# minsis_arduino_mcr.net
KiCad netlist of a schematic drawn in EAGLE
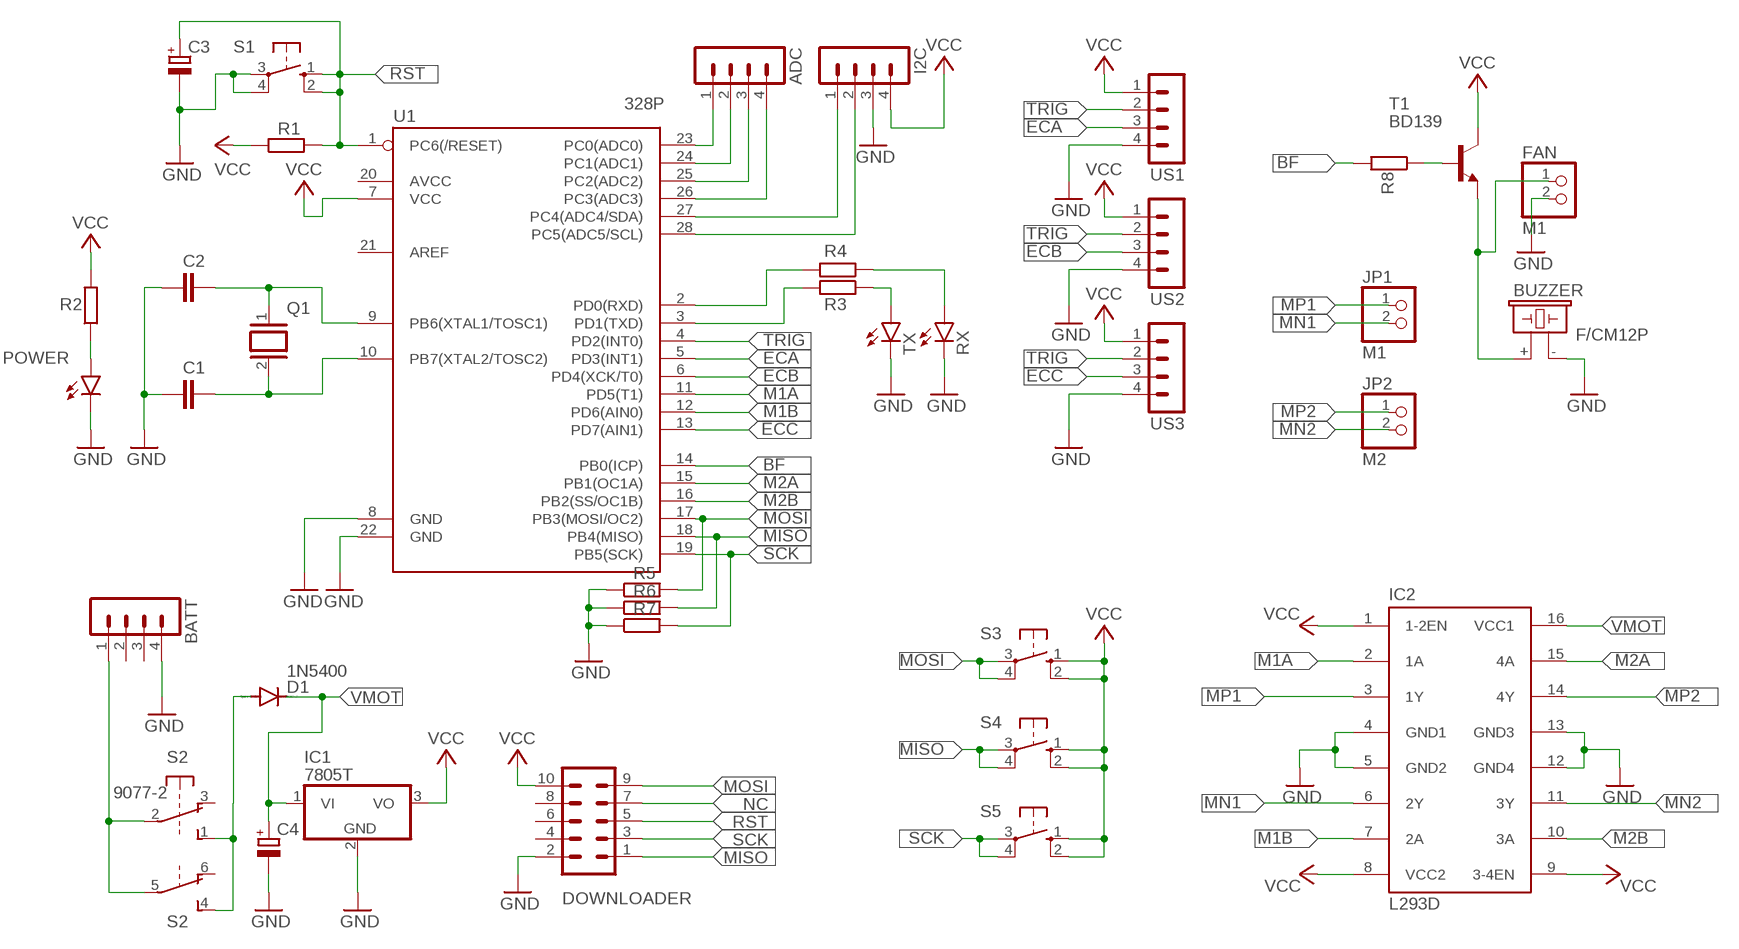
[diagram p0: schematic, sheet 1]

(export (version "E")
  (design (tool "Eeschema 10.0.6"))
  (components
    (comp (ref "ADC")
      (value "MA04-1")
      (footprint "eagle-import:MA04-1")
      (libsource (lib "eagle-import") (part "MA04-1"))
    )
    (comp (ref "BATT")
      (value "MA04-1")
      (footprint "eagle-import:MA04-1")
      (libsource (lib "eagle-import") (part "MA04-1"))
    )
    (comp (ref "BUZZER")
      (value "F/CM12P")
      (footprint "eagle-import:F_CM12P")
      (libsource (lib "eagle-import") (part "F/CM12P"))
    )
    (comp (ref "C1")
      (value "C-EU050-024X044")
      (footprint "eagle-import:C050-024X044")
      (libsource (lib "eagle-import") (part "C-EU050-024X044"))
    )
    (comp (ref "C2")
      (value "C-EU050-024X044")
      (footprint "eagle-import:C050-024X044")
      (libsource (lib "eagle-import") (part "C-EU050-024X044"))
    )
    (comp (ref "C3")
      (value "CPOL-EUE2,5-6E")
      (footprint "eagle-import:E2,5-6E")
      (libsource (lib "eagle-import") (part "CPOL-EUE2,5-6E"))
    )
    (comp (ref "C4")
      (value "CPOL-EUE3.5-8")
      (footprint "eagle-import:E3,5-8")
      (libsource (lib "eagle-import") (part "CPOL-EUE3.5-8"))
    )
    (comp (ref "D1")
      (value "1N5400")
      (footprint "eagle-import:DO201-15")
      (libsource (lib "eagle-import") (part "1N5400"))
    )
    (comp (ref "DOWNLOADER")
      (value "MA05-2")
      (footprint "eagle-import:MA05-2")
      (libsource (lib "eagle-import") (part "MA05-2"))
    )
    (comp (ref "FAN")
      (value "M1")
      (footprint "eagle-import:1X02")
      (libsource (lib "eagle-import") (part "PINHD-1X2"))
    )
    (comp (ref "I2C")
      (value "MA04-1")
      (footprint "eagle-import:MA04-1")
      (libsource (lib "eagle-import") (part "MA04-1"))
    )
    (comp (ref "IC1")
      (value "7805T")
      (footprint "eagle-import:TO220H")
      (libsource (lib "eagle-import") (part "78T05"))
    )
    (comp (ref "IC2")
      (value "L293D")
      (footprint "eagle-import:DIL16")
      (libsource (lib "eagle-import") (part "L293D"))
    )
    (comp (ref "JP1")
      (value "M1")
      (footprint "eagle-import:1X02")
      (libsource (lib "eagle-import") (part "PINHD-1X2"))
    )
    (comp (ref "JP2")
      (value "M2")
      (footprint "eagle-import:1X02")
      (libsource (lib "eagle-import") (part "PINHD-1X2"))
    )
    (comp (ref "POWER")
      (value "LED3MM")
      (footprint "eagle-import:LED3MM")
      (libsource (lib "eagle-import") (part "LED3MM"))
    )
    (comp (ref "Q1")
      (value "XTAL/S")
      (footprint "eagle-import:QS")
      (libsource (lib "eagle-import") (part "XTAL/S"))
    )
    (comp (ref "R1")
      (value "R-EU_0207/7")
      (footprint "eagle-import:0207_7")
      (libsource (lib "eagle-import") (part "R-EU_0207/7"))
    )
    (comp (ref "R2")
      (value "R-EU_0207/7")
      (footprint "eagle-import:0207_7")
      (libsource (lib "eagle-import") (part "R-EU_0207/7"))
    )
    (comp (ref "R3")
      (value "R-EU_0207/7")
      (footprint "eagle-import:0207_7")
      (libsource (lib "eagle-import") (part "R-EU_0207/7"))
    )
    (comp (ref "R4")
      (value "R-EU_0207/7")
      (footprint "eagle-import:0207_7")
      (libsource (lib "eagle-import") (part "R-EU_0207/7"))
    )
    (comp (ref "R5")
      (value "R-EU_0207/7")
      (footprint "eagle-import:0207_7")
      (libsource (lib "eagle-import") (part "R-EU_0207/7"))
    )
    (comp (ref "R6")
      (value "R-EU_0207/7")
      (footprint "eagle-import:0207_7")
      (libsource (lib "eagle-import") (part "R-EU_0207/7"))
    )
    (comp (ref "R7")
      (value "R-EU_0207/7")
      (footprint "eagle-import:0207_7")
      (libsource (lib "eagle-import") (part "R-EU_0207/7"))
    )
    (comp (ref "R8")
      (value "R-EU_0207/7")
      (footprint "eagle-import:0207_7")
      (libsource (lib "eagle-import") (part "R-EU_0207/7"))
    )
    (comp (ref "RX")
      (value "LED3MM")
      (footprint "eagle-import:LED3MM")
      (libsource (lib "eagle-import") (part "LED3MM"))
    )
    (comp (ref "S1")
      (value "10-XX")
      (footprint "eagle-import:B3F-10XX")
      (fields (field (name "MPN") "B3F-1000"))
      (libsource (lib "eagle-import") (part "10-XX"))
    )
    (comp (ref "S2")
      (value "9077-2")
      (footprint "eagle-import:9077-2")
      (libsource (lib "eagle-import") (part "9077-2"))
    )
    (comp (ref "S3")
      (value "10-XX")
      (footprint "eagle-import:B3F-10XX")
      (fields (field (name "MPN") "B3F-1000"))
      (libsource (lib "eagle-import") (part "10-XX"))
    )
    (comp (ref "S4")
      (value "10-XX")
      (footprint "eagle-import:B3F-10XX")
      (fields (field (name "MPN") "B3F-1000"))
      (libsource (lib "eagle-import") (part "10-XX"))
    )
    (comp (ref "S5")
      (value "10-XX")
      (footprint "eagle-import:B3F-10XX")
      (fields (field (name "MPN") "B3F-1000"))
      (libsource (lib "eagle-import") (part "10-XX"))
    )
    (comp (ref "T1")
      (value "BD139")
      (footprint "eagle-import:TO126")
      (libsource (lib "eagle-import") (part "BD139"))
    )
    (comp (ref "TX")
      (value "LED3MM")
      (footprint "eagle-import:LED3MM")
      (libsource (lib "eagle-import") (part "LED3MM"))
    )
    (comp (ref "U1")
      (value "328P")
      (footprint "eagle-import:DIP28")
      (libsource (lib "eagle-import") (part "ATMEGA328P_PDIP"))
    )
    (comp (ref "US1")
      (value "MA04-1")
      (footprint "eagle-import:MA04-1")
      (libsource (lib "eagle-import") (part "MA04-1"))
    )
    (comp (ref "US2")
      (value "MA04-1")
      (footprint "eagle-import:MA04-1")
      (libsource (lib "eagle-import") (part "MA04-1"))
    )
    (comp (ref "US3")
      (value "MA04-1")
      (footprint "eagle-import:MA04-1")
      (libsource (lib "eagle-import") (part "MA04-1"))
    )
  )
  (nets
    (net (code "1") (name "/BF") (class "Default")
      (node (ref "R8") (pin "2") (pinfunction "2_2") (pintype "passive"))
      (node (ref "U1") (pin "14") (pinfunction "PB0(ICP)_14") (pintype "bidirectional"))
    )
    (net (code "2") (name "/ECA") (class "Default")
      (node (ref "U1") (pin "5") (pinfunction "PD3(INT1)_5") (pintype "bidirectional"))
      (node (ref "US1") (pin "3") (pinfunction "3_3") (pintype "passive"))
    )
    (net (code "3") (name "/ECB") (class "Default")
      (node (ref "U1") (pin "6") (pinfunction "PD4(XCK/T0)_6") (pintype "bidirectional"))
      (node (ref "US2") (pin "3") (pinfunction "3_3") (pintype "passive"))
    )
    (net (code "4") (name "/ECC") (class "Default")
      (node (ref "U1") (pin "13") (pinfunction "PD7(AIN1)_13") (pintype "bidirectional"))
      (node (ref "US3") (pin "3") (pinfunction "3_3") (pintype "passive"))
    )
    (net (code "5") (name "/M1A") (class "Default")
      (node (ref "IC2") (pin "2") (pinfunction "1A_2") (pintype "input"))
      (node (ref "U1") (pin "11") (pinfunction "PD5(T1)_11") (pintype "bidirectional"))
    )
    (net (code "6") (name "/M1B") (class "Default")
      (node (ref "IC2") (pin "7") (pinfunction "2A_7") (pintype "input"))
      (node (ref "U1") (pin "12") (pinfunction "PD6(AIN0)_12") (pintype "bidirectional"))
    )
    (net (code "7") (name "/M2A") (class "Default")
      (node (ref "IC2") (pin "15") (pinfunction "4A_15") (pintype "input"))
      (node (ref "U1") (pin "15") (pinfunction "PB1(OC1A)_15") (pintype "bidirectional"))
    )
    (net (code "8") (name "/M2B") (class "Default")
      (node (ref "IC2") (pin "10") (pinfunction "3A_10") (pintype "input"))
      (node (ref "U1") (pin "16") (pinfunction "PB2(SS/OC1B)_16") (pintype "bidirectional"))
    )
    (net (code "9") (name "/MISO") (class "Default")
      (node (ref "DOWNLOADER") (pin "1") (pinfunction "1_1") (pintype "passive"))
      (node (ref "R6") (pin "2") (pinfunction "2_2") (pintype "passive"))
      (node (ref "S4") (pin "3") (pinfunction "P_3") (pintype "passive"))
      (node (ref "S4") (pin "4") (pinfunction "P1_4") (pintype "passive"))
      (node (ref "U1") (pin "18") (pinfunction "PB4(MISO)_18") (pintype "bidirectional"))
    )
    (net (code "10") (name "/MN1") (class "Default")
      (node (ref "IC2") (pin "6") (pinfunction "2Y_6") (pintype "output"))
      (node (ref "JP1") (pin "2") (pinfunction "2_2") (pintype "passive"))
    )
    (net (code "11") (name "/MN2") (class "Default")
      (node (ref "IC2") (pin "11") (pinfunction "3Y_11") (pintype "output"))
      (node (ref "JP2") (pin "2") (pinfunction "2_2") (pintype "passive"))
    )
    (net (code "12") (name "/MOSI") (class "Default")
      (node (ref "DOWNLOADER") (pin "9") (pinfunction "9_9") (pintype "passive"))
      (node (ref "R5") (pin "2") (pinfunction "2_2") (pintype "passive"))
      (node (ref "S3") (pin "3") (pinfunction "P_3") (pintype "passive"))
      (node (ref "S3") (pin "4") (pinfunction "P1_4") (pintype "passive"))
      (node (ref "U1") (pin "17") (pinfunction "PB3(MOSI/OC2)_17") (pintype "bidirectional"))
    )
    (net (code "13") (name "/MP1") (class "Default")
      (node (ref "IC2") (pin "3") (pinfunction "1Y_3") (pintype "output"))
      (node (ref "JP1") (pin "1") (pinfunction "1_1") (pintype "passive"))
    )
    (net (code "14") (name "/MP2") (class "Default")
      (node (ref "IC2") (pin "14") (pinfunction "4Y_14") (pintype "output"))
      (node (ref "JP2") (pin "1") (pinfunction "1_1") (pintype "passive"))
    )
    (net (code "15") (name "/NC") (class "Default")
      (node (ref "DOWNLOADER") (pin "7") (pinfunction "7_7") (pintype "passive"))
    )
    (net (code "16") (name "/RST") (class "Default")
      (node (ref "C3") (pin "+") (pinfunction "+_+") (pintype "passive"))
      (node (ref "DOWNLOADER") (pin "5") (pinfunction "5_5") (pintype "passive"))
      (node (ref "R1") (pin "2") (pinfunction "2_2") (pintype "passive"))
      (node (ref "S1") (pin "1") (pinfunction "S_1") (pintype "passive"))
      (node (ref "S1") (pin "2") (pinfunction "S1_2") (pintype "passive"))
      (node (ref "U1") (pin "1") (pinfunction "PC6(/RESET)_1") (pintype "bidirectional"))
    )
    (net (code "17") (name "/SCK") (class "Default")
      (node (ref "DOWNLOADER") (pin "3") (pinfunction "3_3") (pintype "passive"))
      (node (ref "R7") (pin "2") (pinfunction "2_2") (pintype "passive"))
      (node (ref "S5") (pin "3") (pinfunction "P_3") (pintype "passive"))
      (node (ref "S5") (pin "4") (pinfunction "P1_4") (pintype "passive"))
      (node (ref "U1") (pin "19") (pinfunction "PB5(SCK)_19") (pintype "bidirectional"))
    )
    (net (code "18") (name "/TRIG") (class "Default")
      (node (ref "U1") (pin "4") (pinfunction "PD2(INT0)_4") (pintype "bidirectional"))
      (node (ref "US1") (pin "2") (pinfunction "2_2") (pintype "passive"))
      (node (ref "US2") (pin "2") (pinfunction "2_2") (pintype "passive"))
      (node (ref "US3") (pin "2") (pinfunction "2_2") (pintype "passive"))
    )
    (net (code "19") (name "/VMOT") (class "Default")
      (node (ref "C4") (pin "+") (pinfunction "+_+") (pintype "passive"))
      (node (ref "D1") (pin "C") (pinfunction "C_C") (pintype "passive"))
      (node (ref "IC1") (pin "1") (pinfunction "VI_1") (pintype "input"))
      (node (ref "IC2") (pin "16") (pinfunction "VCC1_16") (pintype "power_in"))
    )
    (net (code "20") (name "GND") (class "Default")
      (node (ref "BATT") (pin "4") (pinfunction "4_4") (pintype "passive"))
      (node (ref "BUZZER") (pin "-") (pinfunction "2_-") (pintype "passive"))
      (node (ref "C1") (pin "1") (pinfunction "1_1") (pintype "passive"))
      (node (ref "C2") (pin "1") (pinfunction "1_1") (pintype "passive"))
      (node (ref "C3") (pin "-") (pinfunction "-_-") (pintype "passive"))
      (node (ref "C4") (pin "-") (pinfunction "-_-") (pintype "passive"))
      (node (ref "DOWNLOADER") (pin "2") (pinfunction "2_2") (pintype "passive"))
      (node (ref "FAN") (pin "2") (pinfunction "2_2") (pintype "passive"))
      (node (ref "I2C") (pin "3") (pinfunction "3_3") (pintype "passive"))
      (node (ref "IC1") (pin "2") (pinfunction "GND_2") (pintype "passive"))
      (node (ref "IC2") (pin "12") (pinfunction "GND4_12") (pintype "power_in"))
      (node (ref "IC2") (pin "13") (pinfunction "GND3_13") (pintype "power_in"))
      (node (ref "IC2") (pin "4") (pinfunction "GND1_4") (pintype "power_in"))
      (node (ref "IC2") (pin "5") (pinfunction "GND2_5") (pintype "power_in"))
      (node (ref "POWER") (pin "K") (pinfunction "C_K") (pintype "passive"))
      (node (ref "R5") (pin "1") (pinfunction "1_1") (pintype "passive"))
      (node (ref "R6") (pin "1") (pinfunction "1_1") (pintype "passive"))
      (node (ref "R7") (pin "1") (pinfunction "1_1") (pintype "passive"))
      (node (ref "RX") (pin "K") (pinfunction "C_K") (pintype "passive"))
      (node (ref "S1") (pin "3") (pinfunction "P_3") (pintype "passive"))
      (node (ref "S1") (pin "4") (pinfunction "P1_4") (pintype "passive"))
      (node (ref "TX") (pin "K") (pinfunction "C_K") (pintype "passive"))
      (node (ref "U1") (pin "22") (pinfunction "GND_22") (pintype "bidirectional"))
      (node (ref "U1") (pin "8") (pinfunction "GND_8") (pintype "bidirectional"))
      (node (ref "US1") (pin "4") (pinfunction "4_4") (pintype "passive"))
      (node (ref "US2") (pin "4") (pinfunction "4_4") (pintype "passive"))
      (node (ref "US3") (pin "4") (pinfunction "4_4") (pintype "passive"))
    )
    (net (code "21") (name "Net-(BUZZER-1)") (class "Default")
      (node (ref "BUZZER") (pin "+") (pinfunction "1_+") (pintype "passive"))
      (node (ref "FAN") (pin "1") (pinfunction "1_1") (pintype "passive"))
      (node (ref "T1") (pin "1") (pinfunction "E_1") (pintype "passive"))
    )
    (net (code "22") (name "Net-(POWER-PadA)") (class "Default")
      (node (ref "POWER") (pin "A") (pinfunction "A_A") (pintype "passive"))
      (node (ref "R2") (pin "1") (pinfunction "1_1") (pintype "passive"))
    )
    (net (code "23") (name "Net-(R3-Pad1)") (class "Default")
      (node (ref "R3") (pin "1") (pinfunction "1_1") (pintype "passive"))
      (node (ref "TX") (pin "A") (pinfunction "A_A") (pintype "passive"))
    )
    (net (code "24") (name "Net-(R4-Pad1)") (class "Default")
      (node (ref "R4") (pin "1") (pinfunction "1_1") (pintype "passive"))
      (node (ref "RX") (pin "A") (pinfunction "A_A") (pintype "passive"))
    )
    (net (code "25") (name "Net-(S2A-P)") (class "Default")
      (node (ref "BATT") (pin "1") (pinfunction "1_1") (pintype "passive"))
      (node (ref "S2") (pin "2") (pinfunction "P_2") (pintype "passive"))
      (node (ref "S2") (pin "5") (pinfunction "P_5") (pintype "passive"))
    )
    (net (code "26") (name "Net-(S2A-S)") (class "Default")
      (node (ref "D1") (pin "A") (pinfunction "A_A") (pintype "passive"))
      (node (ref "S2") (pin "1") (pinfunction "S_1") (pintype "passive"))
      (node (ref "S2") (pin "4") (pinfunction "S_4") (pintype "passive"))
    )
    (net (code "27") (name "Net-(T1-B)") (class "Default")
      (node (ref "R8") (pin "1") (pinfunction "1_1") (pintype "passive"))
      (node (ref "T1") (pin "3") (pinfunction "B_3") (pintype "passive"))
    )
    (net (code "28") (name "Net-(U1-PB6(XTAL1{slash}TOSC1))") (class "Default")
      (node (ref "C2") (pin "2") (pinfunction "2_2") (pintype "passive"))
      (node (ref "Q1") (pin "1") (pinfunction "1_1") (pintype "passive"))
      (node (ref "U1") (pin "9") (pinfunction "PB6(XTAL1/TOSC1)_9") (pintype "bidirectional"))
    )
    (net (code "29") (name "Net-(U1-PB7(XTAL2{slash}TOSC2))") (class "Default")
      (node (ref "C1") (pin "2") (pinfunction "2_2") (pintype "passive"))
      (node (ref "Q1") (pin "2") (pinfunction "2_2") (pintype "passive"))
      (node (ref "U1") (pin "10") (pinfunction "PB7(XTAL2/TOSC2)_10") (pintype "bidirectional"))
    )
    (net (code "30") (name "Net-(U1-PC0(ADC0))") (class "Default")
      (node (ref "ADC") (pin "1") (pinfunction "1_1") (pintype "passive"))
      (node (ref "U1") (pin "23") (pinfunction "PC0(ADC0)_23") (pintype "bidirectional"))
    )
    (net (code "31") (name "Net-(U1-PC1(ADC1))") (class "Default")
      (node (ref "ADC") (pin "2") (pinfunction "2_2") (pintype "passive"))
      (node (ref "U1") (pin "24") (pinfunction "PC1(ADC1)_24") (pintype "bidirectional"))
    )
    (net (code "32") (name "Net-(U1-PC2(ADC2))") (class "Default")
      (node (ref "ADC") (pin "3") (pinfunction "3_3") (pintype "passive"))
      (node (ref "U1") (pin "25") (pinfunction "PC2(ADC2)_25") (pintype "bidirectional"))
    )
    (net (code "33") (name "Net-(U1-PC3(ADC3))") (class "Default")
      (node (ref "ADC") (pin "4") (pinfunction "4_4") (pintype "passive"))
      (node (ref "U1") (pin "26") (pinfunction "PC3(ADC3)_26") (pintype "bidirectional"))
    )
    (net (code "34") (name "Net-(U1-PC4(ADC4{slash}SDA))") (class "Default")
      (node (ref "I2C") (pin "1") (pinfunction "1_1") (pintype "passive"))
      (node (ref "U1") (pin "27") (pinfunction "PC4(ADC4/SDA)_27") (pintype "bidirectional"))
    )
    (net (code "35") (name "Net-(U1-PC5(ADC5{slash}SCL))") (class "Default")
      (node (ref "I2C") (pin "2") (pinfunction "2_2") (pintype "passive"))
      (node (ref "U1") (pin "28") (pinfunction "PC5(ADC5/SCL)_28") (pintype "bidirectional"))
    )
    (net (code "36") (name "Net-(U1-PD0(RXD))") (class "Default")
      (node (ref "R4") (pin "2") (pinfunction "2_2") (pintype "passive"))
      (node (ref "U1") (pin "2") (pinfunction "PD0(RXD)_2") (pintype "bidirectional"))
    )
    (net (code "37") (name "Net-(U1-PD1(TXD))") (class "Default")
      (node (ref "R3") (pin "2") (pinfunction "2_2") (pintype "passive"))
      (node (ref "U1") (pin "3") (pinfunction "PD1(TXD)_3") (pintype "bidirectional"))
    )
    (net (code "38") (name "VCC") (class "Default")
      (node (ref "DOWNLOADER") (pin "10") (pinfunction "10_10") (pintype "passive"))
      (node (ref "I2C") (pin "4") (pinfunction "4_4") (pintype "passive"))
      (node (ref "IC1") (pin "3") (pinfunction "VO_3") (pintype "passive"))
      (node (ref "IC2") (pin "1") (pinfunction "1-2EN_1") (pintype "input"))
      (node (ref "IC2") (pin "8") (pinfunction "VCC2_8") (pintype "power_in"))
      (node (ref "IC2") (pin "9") (pinfunction "3-4EN_9") (pintype "input"))
      (node (ref "R1") (pin "1") (pinfunction "1_1") (pintype "passive"))
      (node (ref "R2") (pin "2") (pinfunction "2_2") (pintype "passive"))
      (node (ref "S3") (pin "1") (pinfunction "S_1") (pintype "passive"))
      (node (ref "S3") (pin "2") (pinfunction "S1_2") (pintype "passive"))
      (node (ref "S4") (pin "1") (pinfunction "S_1") (pintype "passive"))
      (node (ref "S4") (pin "2") (pinfunction "S1_2") (pintype "passive"))
      (node (ref "S5") (pin "1") (pinfunction "S_1") (pintype "passive"))
      (node (ref "S5") (pin "2") (pinfunction "S1_2") (pintype "passive"))
      (node (ref "T1") (pin "2") (pinfunction "C_2") (pintype "passive"))
      (node (ref "U1") (pin "7") (pinfunction "VCC_7") (pintype "bidirectional"))
      (node (ref "US1") (pin "1") (pinfunction "1_1") (pintype "passive"))
      (node (ref "US2") (pin "1") (pinfunction "1_1") (pintype "passive"))
      (node (ref "US3") (pin "1") (pinfunction "1_1") (pintype "passive"))
    )
    (net (code "39") (name "unconnected-(BATT-Pad2)") (class "Default")
      (node (ref "BATT") (pin "2") (pinfunction "2_2") (pintype "passive"))
    )
    (net (code "40") (name "unconnected-(BATT-Pad3)") (class "Default")
      (node (ref "BATT") (pin "3") (pinfunction "3_3") (pintype "passive"))
    )
    (net (code "41") (name "unconnected-(DOWNLOADER-Pad4)") (class "Default")
      (node (ref "DOWNLOADER") (pin "4") (pinfunction "4_4") (pintype "passive"))
    )
    (net (code "42") (name "unconnected-(DOWNLOADER-Pad6)") (class "Default")
      (node (ref "DOWNLOADER") (pin "6") (pinfunction "6_6") (pintype "passive"))
    )
    (net (code "43") (name "unconnected-(DOWNLOADER-Pad8)") (class "Default")
      (node (ref "DOWNLOADER") (pin "8") (pinfunction "8_8") (pintype "passive"))
    )
    (net (code "44") (name "unconnected-(S2A-O-Pad3)") (class "Default")
      (node (ref "S2") (pin "3") (pinfunction "O_3") (pintype "passive"))
    )
    (net (code "45") (name "unconnected-(S2B-O-Pad6)") (class "Default")
      (node (ref "S2") (pin "6") (pinfunction "O_6") (pintype "passive"))
    )
    (net (code "46") (name "unconnected-(U1-AREF-Pad21)") (class "Default")
      (node (ref "U1") (pin "21") (pinfunction "AREF_21") (pintype "bidirectional"))
    )
    (net (code "47") (name "unconnected-(U1-AVCC-Pad20)") (class "Default")
      (node (ref "U1") (pin "20") (pinfunction "AVCC_20") (pintype "bidirectional"))
    )
  )
)
